# MCU.net
KiCad netlist of a schematic drawn in Altium Designer
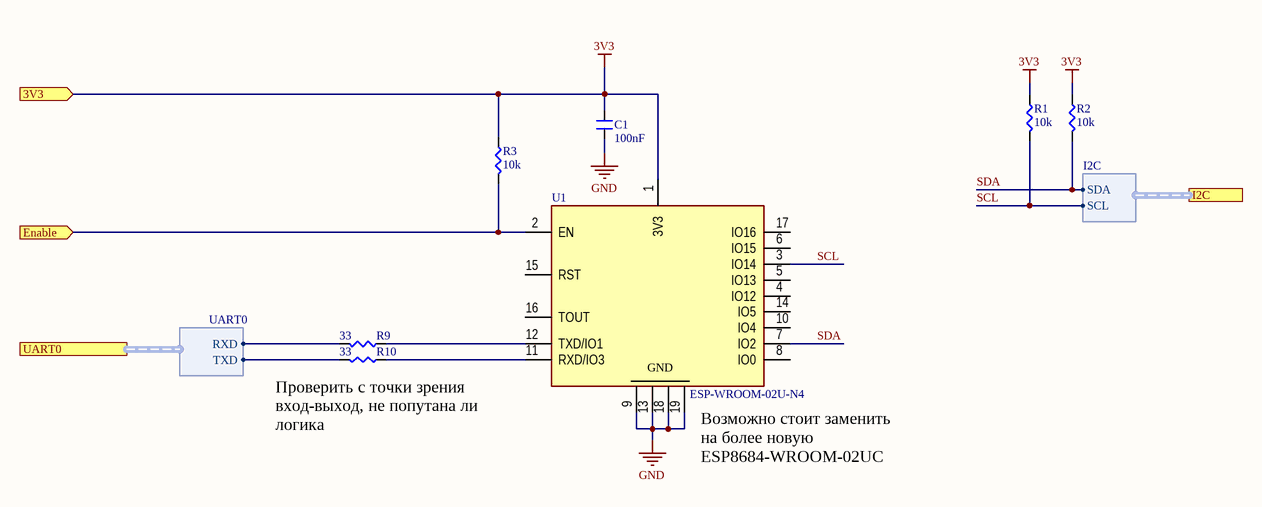
[diagram p0: MCU.SchDoc]

(export (version "E")
  (design (tool "Eeschema 10.0.6"))
  (components
    (comp (ref "C1")
      (value "100nF")
      (footprint "CAP0603")
      (description "Tolerance ±10%\nRated Voltage 50Vdc\nTemperature 0±30ppm/℃")
      (fields (field (name "PART NUMBER") "GCM188R71H104KA57J") (field (name "TOLERANCE") "10%"))
      (libsource (lib "Lib_Kam") (part "Capacitor"))
    )
    (comp (ref "R1")
      (value "10k")
      (footprint "RES0603")
      (description "Tolerance ±1%\nPower (Watts) 0.1W, 1/10W\nTemperature Coefficient ±100ppm/°C")
      (fields (field (name "PART NUMBER") "CR0603-FX-1002ELF") (field (name "TOLERANCE") "1%"))
      (libsource (lib "Lib_Kam") (part "Resistor"))
    )
    (comp (ref "R2")
      (value "10k")
      (footprint "RES0603")
      (description "Tolerance ±1%\nPower (Watts) 0.1W, 1/10W\nTemperature Coefficient ±100ppm/°C")
      (fields (field (name "PART NUMBER") "CR0603-FX-1002ELF") (field (name "TOLERANCE") "1%"))
      (libsource (lib "Lib_Kam") (part "Resistor"))
    )
    (comp (ref "R3")
      (value "10k")
      (footprint "RES0603")
      (description "Tolerance ±1%\nPower (Watts) 0.1W, 1/10W\nTemperature Coefficient ±100ppm/°C")
      (fields (field (name "PART NUMBER") "CR0603-FX-1002ELF") (field (name "TOLERANCE") "1%"))
      (libsource (lib "Lib_Kam") (part "Resistor"))
    )
    (comp (ref "R9")
      (value "33")
      (footprint "RES0603")
      (description "Tolerance ±1%\nPower (Watts) 0.1W, 1/10W\nTemperature Coefficient ±100ppm/°C")
      (fields (field (name "PART NUMBER") "CR0603FX-33R0ELF") (field (name "TOLERANCE") "1%"))
      (libsource (lib "Lib_Kam") (part "Resistor"))
    )
    (comp (ref "R10")
      (value "33")
      (footprint "RES0603")
      (description "Tolerance ±1%\nPower (Watts) 0.1W, 1/10W\nTemperature Coefficient ±100ppm/°C")
      (fields (field (name "PART NUMBER") "CR0603FX-33R0ELF") (field (name "TOLERANCE") "1%"))
      (libsource (lib "Lib_Kam") (part "Resistor"))
    )
    (comp (ref "U1")
      (value "ESP-WROOM-02U-N4")
      (footprint "ESP-WROOM-02U-N4")
      (fields (field (name "MANUFACTURER") "Espressif Systems"))
      (libsource (lib "Lib_Kam") (part "ESP-WROOM-02U"))
    )
  )
  (nets
    (net (code "3") (name "/Enable") (class "Default")
      (node (ref "R3") (pin "1") (pintype "passive"))
      (node (ref "U1") (pin "2") (pinfunction "EN_2") (pintype "passive"))
    )
    (net (code "4") (name "/RXD") (class "Default") (node (ref "R9") (pin "1") (pintype "passive")))
    (net (code "5") (name "/SCL") (class "Default")
      (node (ref "R1") (pin "1") (pintype "passive"))
      (node (ref "U1") (pin "3") (pinfunction "IO14_3") (pintype "passive"))
    )
    (net (code "6") (name "/SDA") (class "Default")
      (node (ref "R2") (pin "1") (pintype "passive"))
      (node (ref "U1") (pin "7") (pinfunction "IO2_7") (pintype "passive"))
    )
    (net (code "7") (name "/TXD") (class "Default") (node (ref "R10") (pin "1") (pintype "passive")))
    (net (code "10") (name "3V3") (class "Default")
      (node (ref "C1") (pin "2") (pinfunction "2_2") (pintype "passive"))
      (node (ref "R1") (pin "2") (pintype "passive"))
      (node (ref "R2") (pin "2") (pintype "passive"))
      (node (ref "R3") (pin "2") (pintype "passive"))
      (node (ref "U1") (pin "1") (pinfunction "3V3_1") (pintype "passive"))
    )
    (net (code "11") (name "GND") (class "Default")
      (node (ref "C1") (pin "1") (pinfunction "2_1") (pintype "passive"))
      (node (ref "U1") (pin "13") (pinfunction "GND_13") (pintype "passive"))
      (node (ref "U1") (pin "18") (pinfunction "GND_18") (pintype "passive"))
      (node (ref "U1") (pin "19") (pinfunction "GND_19") (pintype "passive"))
      (node (ref "U1") (pin "9") (pinfunction "GND_9") (pintype "passive"))
    )
    (net (code "12") (name "Net-(U1-RXD{slash}IO3)") (class "Default")
      (node (ref "R10") (pin "2") (pintype "passive"))
      (node (ref "U1") (pin "11") (pinfunction "RXD/IO3_11") (pintype "passive"))
    )
    (net (code "13") (name "Net-(U1-TXD{slash}IO1)") (class "Default")
      (node (ref "R9") (pin "2") (pintype "passive"))
      (node (ref "U1") (pin "12") (pinfunction "TXD/IO1_12") (pintype "passive"))
    )
    (net (code "14") (name "unconnected-(U1-IO0-Pad8)") (class "Default")
      (node (ref "U1") (pin "8") (pinfunction "IO0_8") (pintype "passive"))
    )
    (net (code "15") (name "unconnected-(U1-IO4-Pad10)") (class "Default")
      (node (ref "U1") (pin "10") (pinfunction "IO4_10") (pintype "passive"))
    )
    (net (code "16") (name "unconnected-(U1-IO5-Pad14)") (class "Default")
      (node (ref "U1") (pin "14") (pinfunction "IO5_14") (pintype "passive"))
    )
    (net (code "17") (name "unconnected-(U1-IO12-Pad4)") (class "Default")
      (node (ref "U1") (pin "4") (pinfunction "IO12_4") (pintype "passive"))
    )
    (net (code "18") (name "unconnected-(U1-IO13-Pad5)") (class "Default")
      (node (ref "U1") (pin "5") (pinfunction "IO13_5") (pintype "passive"))
    )
    (net (code "19") (name "unconnected-(U1-IO15-Pad6)") (class "Default")
      (node (ref "U1") (pin "6") (pinfunction "IO15_6") (pintype "passive"))
    )
    (net (code "20") (name "unconnected-(U1-IO16-Pad17)") (class "Default")
      (node (ref "U1") (pin "17") (pinfunction "IO16_17") (pintype "passive"))
    )
    (net (code "21") (name "unconnected-(U1-RST-Pad15)") (class "Default")
      (node (ref "U1") (pin "15") (pinfunction "RST_15") (pintype "passive"))
    )
    (net (code "22") (name "unconnected-(U1-TOUT-Pad16)") (class "Default")
      (node (ref "U1") (pin "16") (pinfunction "TOUT_16") (pintype "passive"))
    )
  )
)
